# fasciaMainBoard_V0.net
KiCad netlist of a schematic drawn in EAGLE
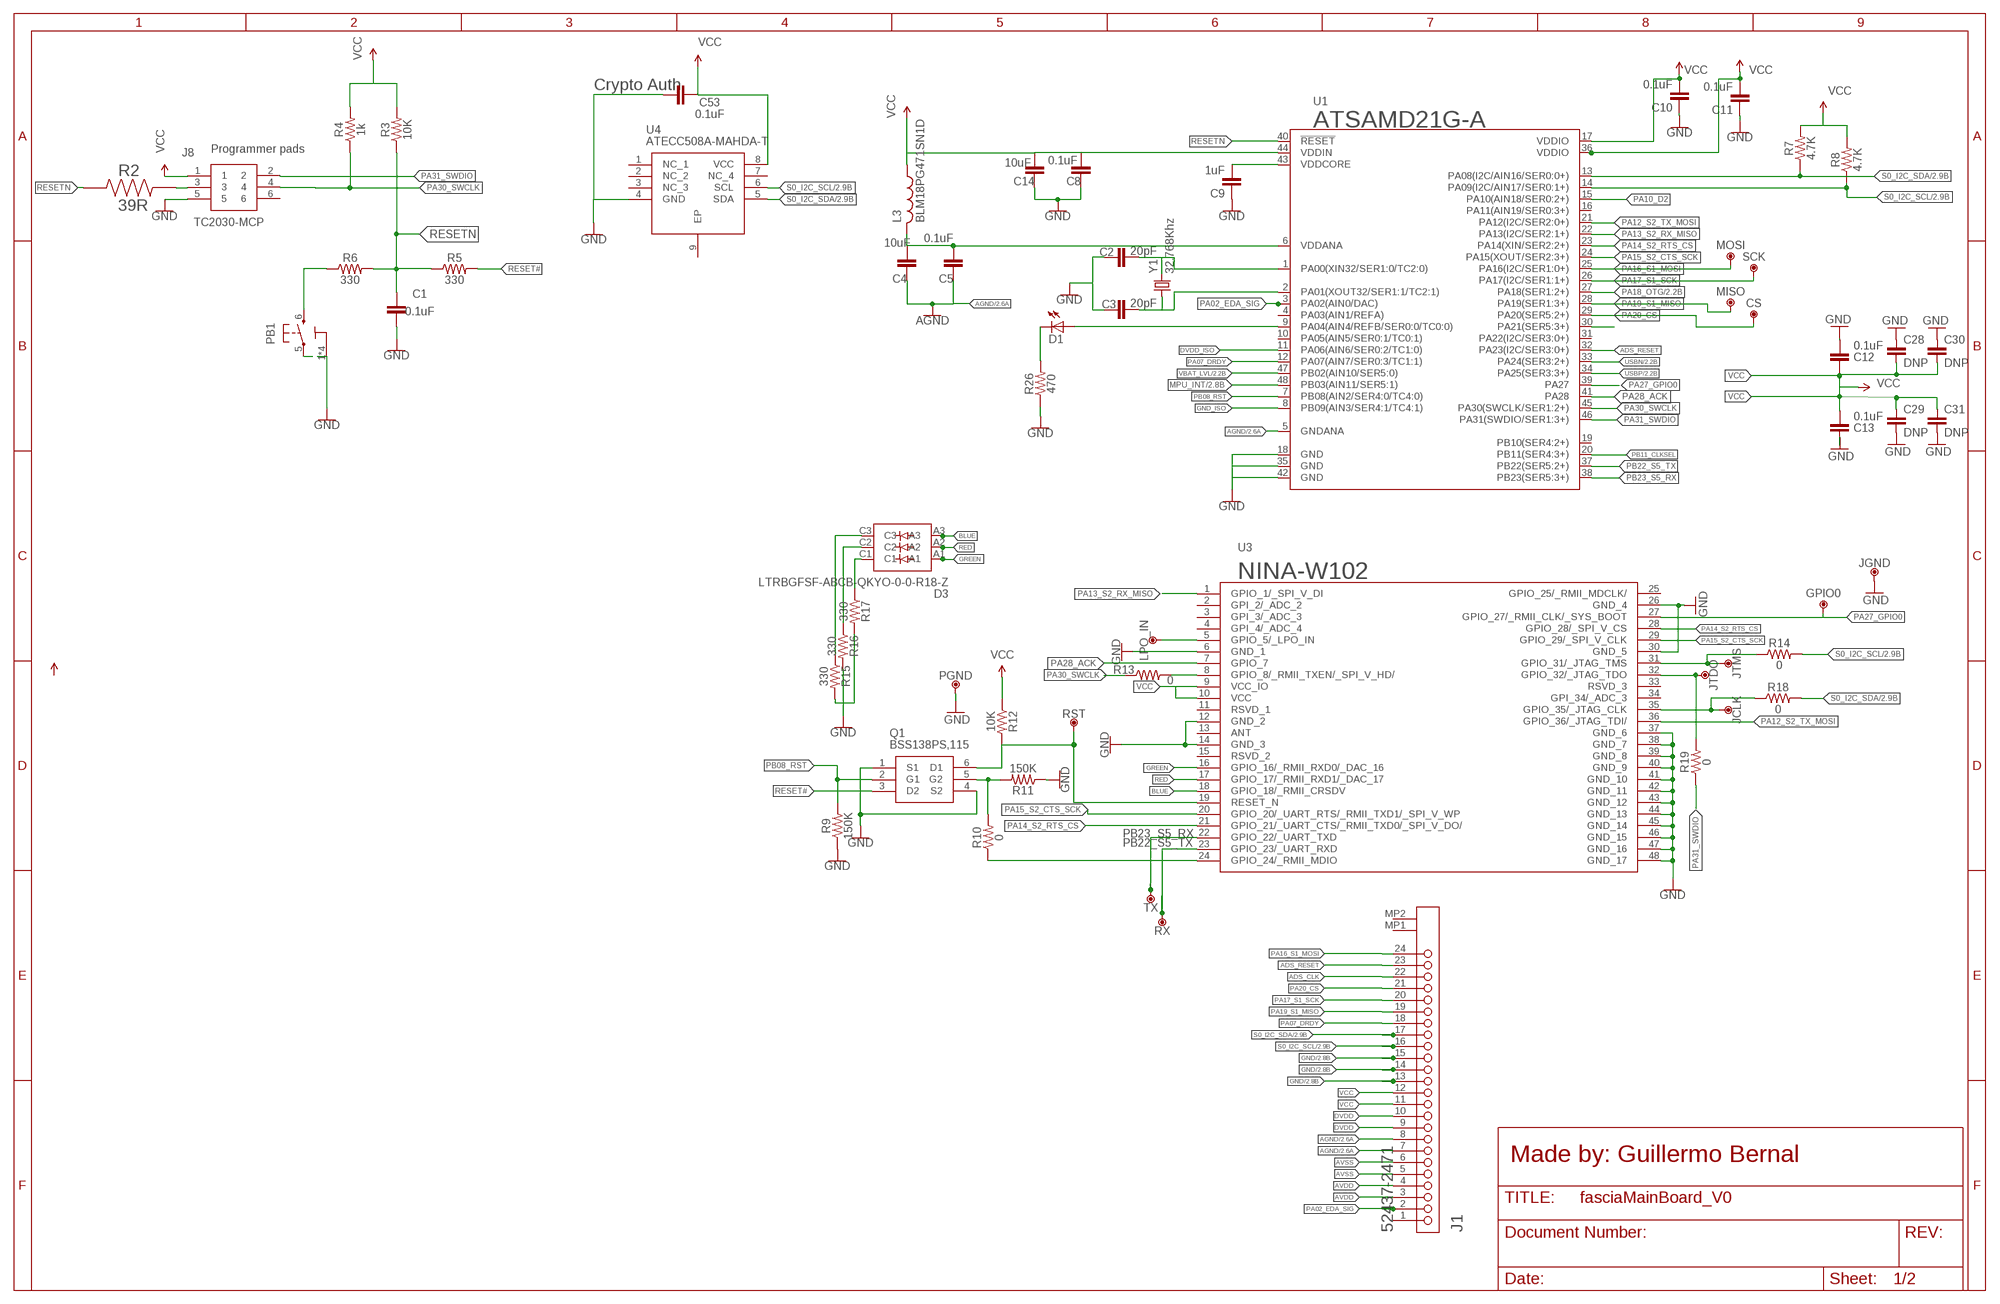
[diagram p0: schematic, sheet 1]
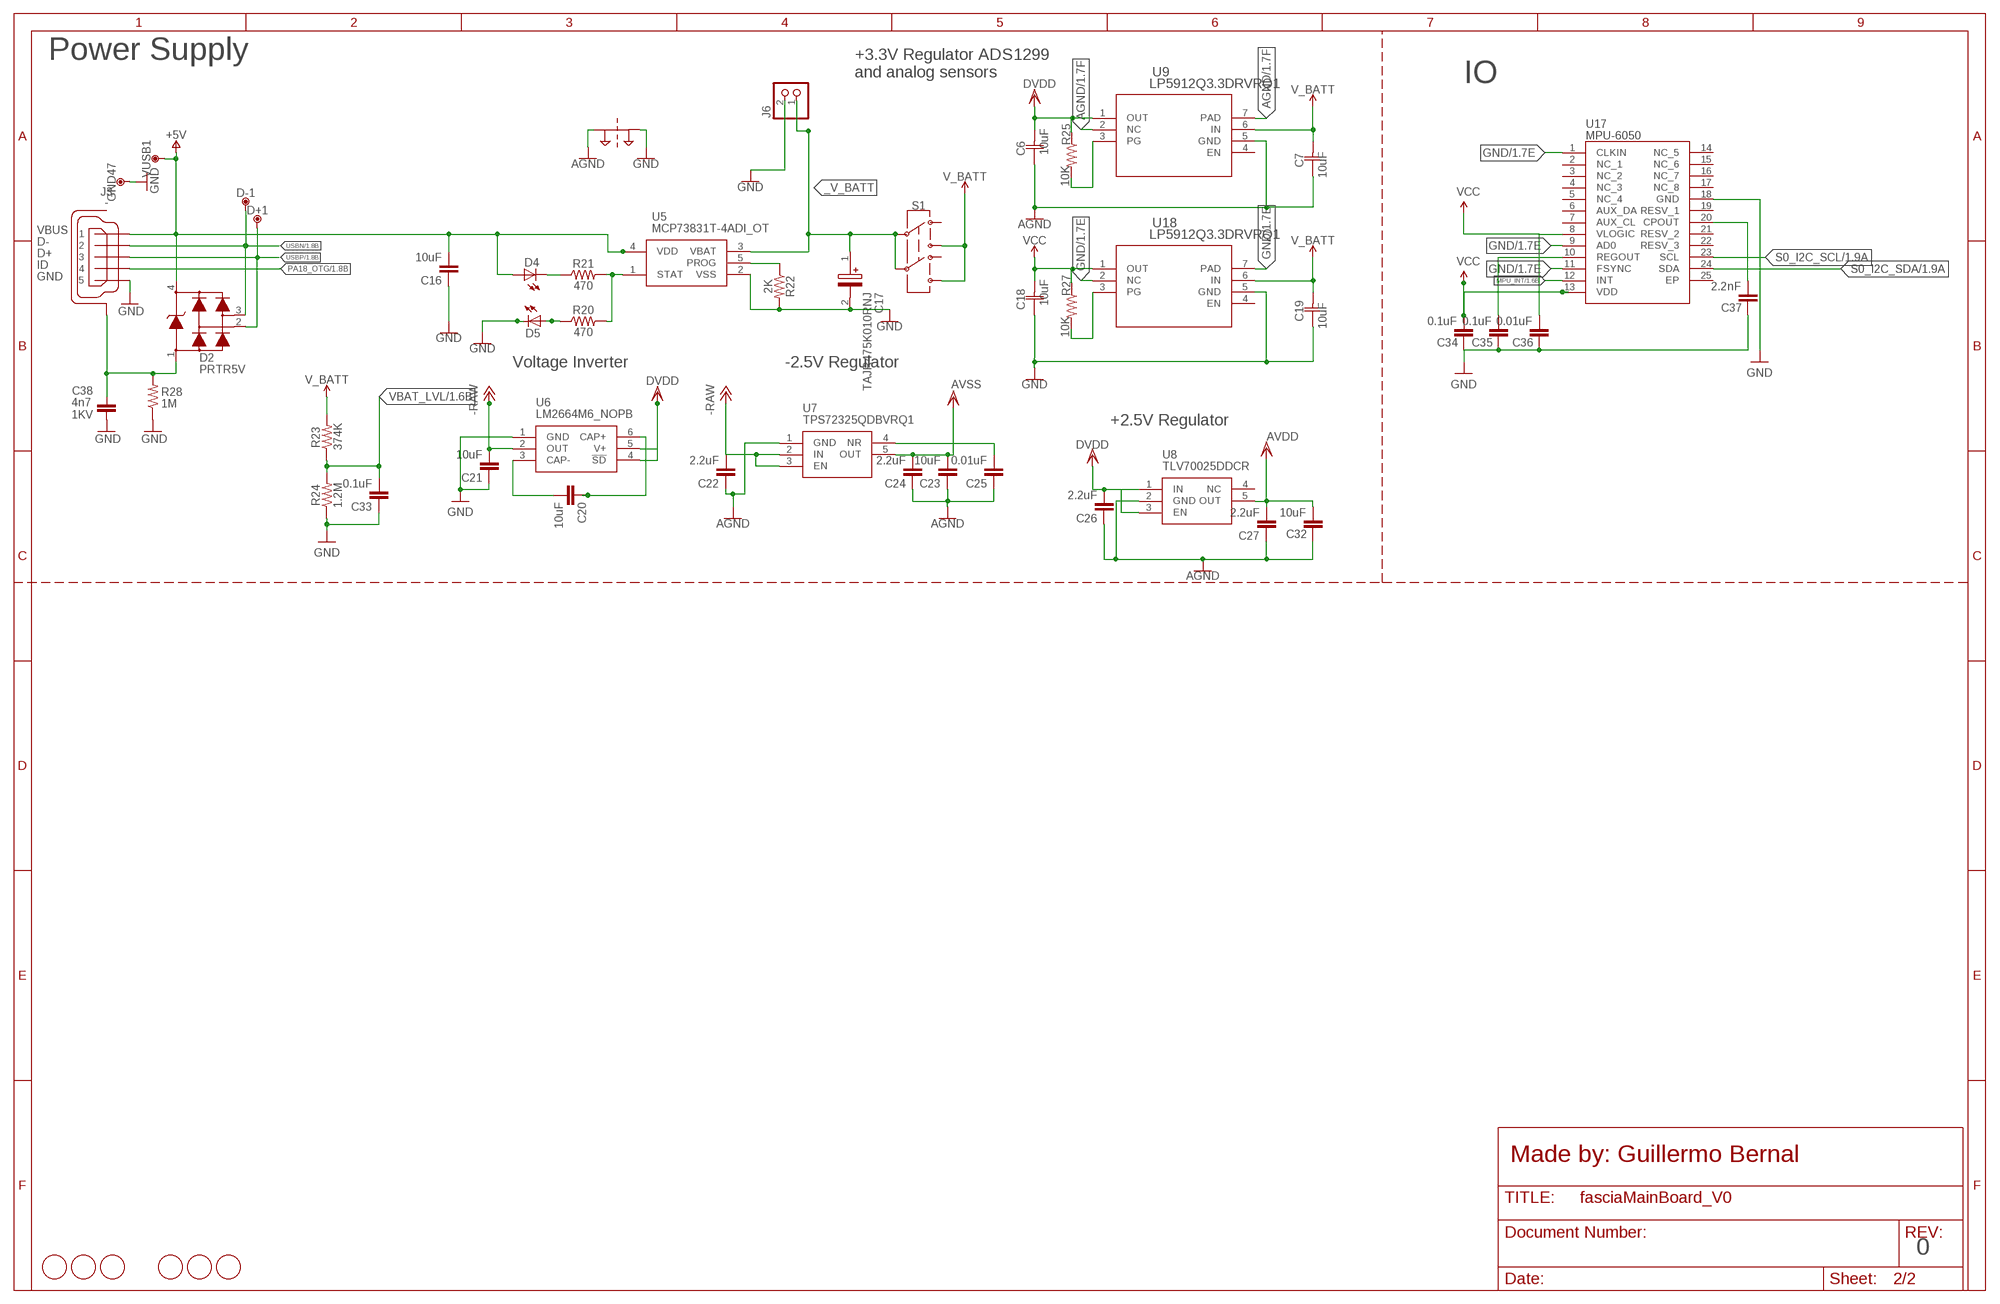
[diagram p1: schematic, sheet 2]

(export (version "E")
  (design (tool "Eeschema 10.0.6"))
  (components
    (comp (ref "C6")
      (value "10uF")
      (footprint "eagle-import:CAP_CL10-L")
      (fields (field (name "MANUFACTURER_PART_NUMBER") "CL10B106MQ8NRNC"))
      (libsource (lib "eagle-import") (part "CL10B106MQ8NRNCCAP_CL10-L"))
    )
    (comp (ref "C7")
      (value "10uF")
      (footprint "eagle-import:CAP_CL10-L")
      (fields (field (name "MANUFACTURER_PART_NUMBER") "CL10B106MQ8NRNC"))
      (libsource (lib "eagle-import") (part "CL10B106MQ8NRNCCAP_CL10-L"))
    )
    (comp (ref "C16")
      (value "10uF")
      (footprint "eagle-import:0603")
      (libsource (lib "eagle-import") (part "10UF-0603-6.3V-20%"))
    )
    (comp (ref "C17")
      (value "TAJR475K010RNJ")
      (footprint "eagle-import:CAPPM2014X120N")
      (fields
        (field (name "MOUSER_PART_NUMBER") "581-TAJR475K010R")
        (field (name "RS_PART_NUMBER") "1355409P")
      )
      (libsource (lib "eagle-import") (part "TAJR475K010RNJ"))
    )
    (comp (ref "C18")
      (value "10uF")
      (footprint "eagle-import:CAP_CL10-L")
      (fields (field (name "MANUFACTURER_PART_NUMBER") "CL10B106MQ8NRNC"))
      (libsource (lib "eagle-import") (part "CL10B106MQ8NRNCCAP_CL10-L"))
    )
    (comp (ref "C19")
      (value "10uF")
      (footprint "eagle-import:CAP_CL10-L")
      (fields (field (name "MANUFACTURER_PART_NUMBER") "CL10B106MQ8NRNC"))
      (libsource (lib "eagle-import") (part "CL10B106MQ8NRNCCAP_CL10-L"))
    )
    (comp (ref "C20")
      (value "10uF")
      (footprint "eagle-import:0603")
      (libsource (lib "eagle-import") (part "10UF-0603-6.3V-20%"))
    )
    (comp (ref "C21")
      (value "10uF")
      (footprint "eagle-import:0603")
      (libsource (lib "eagle-import") (part "10UF-0603-6.3V-20%"))
    )
    (comp (ref "C22")
      (value "2.2uF")
      (footprint "eagle-import:0402-TIGHT")
      (libsource (lib "eagle-import") (part "2.2UF-0402T-16V-10%"))
    )
    (comp (ref "C23")
      (value "10uF")
      (footprint "eagle-import:0603")
      (libsource (lib "eagle-import") (part "10UF-0603-6.3V-20%"))
    )
    (comp (ref "C24")
      (value "2.2uF")
      (footprint "eagle-import:0402-TIGHT")
      (libsource (lib "eagle-import") (part "2.2UF-0402T-16V-10%"))
    )
    (comp (ref "C25")
      (value "0.01uF")
      (footprint "eagle-import:0402-TIGHT")
      (libsource (lib "eagle-import") (part "0.01UF-0402T-16V-10%"))
    )
    (comp (ref "C26")
      (value "2.2uF")
      (footprint "eagle-import:0402-TIGHT")
      (libsource (lib "eagle-import") (part "2.2UF-0402T-16V-10%"))
    )
    (comp (ref "C27")
      (value "2.2uF")
      (footprint "eagle-import:0402-TIGHT")
      (libsource (lib "eagle-import") (part "2.2UF-0402T-16V-10%"))
    )
    (comp (ref "C32")
      (value "10uF")
      (footprint "eagle-import:0603")
      (libsource (lib "eagle-import") (part "10UF-0603-6.3V-20%"))
    )
    (comp (ref "C33")
      (value "0.1uF")
      (footprint "eagle-import:0402-TIGHT")
      (libsource (lib "eagle-import") (part "0.1UF-0402T-16V-10%"))
    )
    (comp (ref "C34")
      (value "0.1uF")
      (footprint "eagle-import:0402-TIGHT")
      (libsource (lib "eagle-import") (part "0.1UF-0402T-16V-10%"))
    )
    (comp (ref "C35")
      (value "0.1uF")
      (footprint "eagle-import:0402-TIGHT")
      (libsource (lib "eagle-import") (part "0.1UF-0402T-16V-10%"))
    )
    (comp (ref "C36")
      (value "0.01uF")
      (footprint "eagle-import:0402-TIGHT")
      (libsource (lib "eagle-import") (part "0.01UF-0402T-16V-10%"))
    )
    (comp (ref "C37")
      (value "2.2nF")
      (footprint "eagle-import:0402-TIGHT")
      (libsource (lib "eagle-import") (part "2.2NF-0402T-16V-10%"))
    )
    (comp (ref "C38")
      (value "4n7")
      (footprint "eagle-import:0805-R2013X50N")
      (fields (field (name "MANUFACTURER") "Kemet") (field (name "VOLTAGE") "1KV"))
      (libsource (lib "eagle-import") (part "C-08054.7NF"))
    )
    (comp (ref "D+1")
      (value "DNP")
      (footprint "eagle-import:TP-1.00MM")
      (libsource (lib "eagle-import") (part "TPTP-1.00MM"))
    )
    (comp (ref "D-1")
      (value "DNP")
      (footprint "eagle-import:TP-1.00MM")
      (libsource (lib "eagle-import") (part "TPTP-1.00MM"))
    )
    (comp (ref "D2")
      (value "PRTR5V")
      (footprint "eagle-import:SOT190P230X110-4N")
      (fields (field (name "MANUFACTURER") "NXP"))
      (libsource (lib "eagle-import") (part "PRTR5V0U2X,215"))
    )
    (comp (ref "D4")
      (value "LEDCHIPLED_0603")
      (footprint "eagle-import:CHIPLED_0603")
      (libsource (lib "eagle-import") (part "LEDCHIPLED_0603"))
    )
    (comp (ref "D5")
      (value "LEDCHIPLED_0603")
      (footprint "eagle-import:CHIPLED_0603")
      (libsource (lib "eagle-import") (part "LEDCHIPLED_0603"))
    )
    (comp (ref "FD1")
      (value "DNP")
      (footprint "eagle-import:FD-1-1.5")
      (libsource (lib "eagle-import") (part "FIDUCIAL-1.5MM"))
    )
    (comp (ref "FD2")
      (value "DNP")
      (footprint "eagle-import:FD-1-1.5")
      (libsource (lib "eagle-import") (part "FIDUCIAL-1.5MM"))
    )
    (comp (ref "FD3")
      (value "DNP")
      (footprint "eagle-import:FD-1-1.5")
      (libsource (lib "eagle-import") (part "FIDUCIAL-1.5MM"))
    )
    (comp (ref "FD4")
      (value "DNP")
      (footprint "eagle-import:FD-1-1.5")
      (libsource (lib "eagle-import") (part "FIDUCIAL-1.5MM"))
    )
    (comp (ref "FD5")
      (value "DNP")
      (footprint "eagle-import:FD-1-1.5")
      (libsource (lib "eagle-import") (part "FIDUCIAL-1.5MM"))
    )
    (comp (ref "FD6")
      (value "DNP")
      (footprint "eagle-import:FD-1-1.5")
      (libsource (lib "eagle-import") (part "FIDUCIAL-1.5MM"))
    )
    (comp (ref "GND47")
      (value "DNP")
      (footprint "eagle-import:TP-1.00MM")
      (libsource (lib "eagle-import") (part "TPTP-1.00MM"))
    )
    (comp (ref "J3")
      (value "-")
      (footprint "eagle-import:ZX62-AB-5PA")
      (fields (field (name "MANUFACTURER") "Hirose"))
      (libsource (lib "eagle-import") (part "USB-MICRO"))
    )
    (comp (ref "J6")
      (value "JST_2PIN-SMT-RA")
      (footprint "eagle-import:JST-PH-2-SMT-RA")
      (libsource (lib "eagle-import") (part "JST_2PIN-SMT-RA"))
    )
    (comp (ref "R20")
      (value "470")
      (footprint "eagle-import:0402-TIGHT")
      (libsource (lib "eagle-import") (part "470"))
    )
    (comp (ref "R21")
      (value "470")
      (footprint "eagle-import:0402-TIGHT")
      (libsource (lib "eagle-import") (part "470"))
    )
    (comp (ref "R22")
      (value "2K")
      (footprint "eagle-import:0402-TIGHT")
      (libsource (lib "eagle-import") (part "2K"))
    )
    (comp (ref "R23")
      (value "374K")
      (footprint "eagle-import:0402-TIGHT")
      (libsource (lib "eagle-import") (part "374K"))
    )
    (comp (ref "R24")
      (value "1.2M")
      (footprint "eagle-import:0402")
      (libsource (lib "eagle-import") (part "1.2M-0402-1/10W-1%"))
    )
    (comp (ref "R25")
      (value "10K")
      (footprint "eagle-import:0402-TIGHT")
      (libsource (lib "eagle-import") (part "10K"))
    )
    (comp (ref "R27")
      (value "10K")
      (footprint "eagle-import:0402-TIGHT")
      (libsource (lib "eagle-import") (part "10K"))
    )
    (comp (ref "R28")
      (value "1M")
      (footprint "eagle-import:0402-TIGHT")
      (libsource (lib "eagle-import") (part "1M"))
    )
    (comp (ref "S1")
      (value "SWITCH-DPDT-SMD-AYZ0202")
      (footprint "eagle-import:SWITCH_DPDT_SMD_AYZ0202")
      (libsource (lib "eagle-import") (part "SWITCH-DPDT-SMD-AYZ0202"))
    )
    (comp (ref "SUPPLY1")
      (value "2PT_GND_TIE")
      (footprint "eagle-import:2PT_GND_TIE")
      (libsource (lib "eagle-import") (part "2PT_GND_TIE"))
    )
    (comp (ref "U5")
      (value "MCP73831T-4ADI_OT")
      (footprint "eagle-import:SOT95P270X145-5N")
      (fields
        (field (name "MANUFACTURER_PART_NUMBER") "MCP73831T-4ADI/OT")
        (field (name "MOUSER_PART_NUMBER") "579-MCP73831T4ADIOT")
      )
      (libsource (lib "eagle-import") (part "MCP73831T-4ADI_OT"))
    )
    (comp (ref "U6")
      (value "LM2664M6_NOPB")
      (footprint "eagle-import:SOT95P280X145-6N")
      (fields
        (field (name "MANUFACTURER_PART_NUMBER") "LM2664M6/NOPB")
        (field (name "MOUSER_PART_NUMBER") "926-LM2664M6/NOPB")
        (field (name "RS_PART_NUMBER") "5358792P")
      )
      (libsource (lib "eagle-import") (part "LM2664M6_NOPB"))
    )
    (comp (ref "U7")
      (value "TPS72325QDBVRQ1")
      (footprint "eagle-import:SOT96P230X110-5N")
      (libsource (lib "eagle-import") (part "TPS72325QDBVRQ1"))
    )
    (comp (ref "U8")
      (value "TLV70025DDCR")
      (footprint "eagle-import:SOT95P280X110-5N")
      (fields (field (name "MOUSER_PART_NUMBER") "595-TLV70025DDCR"))
      (libsource (lib "eagle-import") (part "TLV70025DDCR"))
    )
    (comp (ref "U9")
      (value "LP5912Q3.3DRVRQ1")
      (footprint "eagle-import:DRV0006A")
      (libsource (lib "eagle-import") (part "LP5912Q3.3DRVRQ1"))
    )
    (comp (ref "U17")
      (value "MPU-6050")
      (footprint "eagle-import:MPU6050")
      (fields (field (name "MOUSER_PART_NUMBER") "410-MPU-6050"))
      (libsource (lib "eagle-import") (part "MPU-6050"))
    )
    (comp (ref "U18")
      (value "LP5912Q3.3DRVRQ1")
      (footprint "eagle-import:DRV0006A")
      (libsource (lib "eagle-import") (part "LP5912Q3.3DRVRQ1"))
    )
    (comp (ref "VUSB1")
      (value "DNP")
      (footprint "eagle-import:TP-1.00MM")
      (libsource (lib "eagle-import") (part "TPTP-1.00MM"))
    )
    (comp (ref "C1")
      (value "0.1uF")
      (footprint "eagle-import:0402-TIGHT")
      (libsource (lib "eagle-import") (part "0.1UF-0402T-16V-10%"))
    )
    (comp (ref "C2")
      (value "20pF")
      (footprint "eagle-import:0402-TIGHT")
      (libsource (lib "eagle-import") (part "20PF-0402T-16V-10%"))
    )
    (comp (ref "C3")
      (value "20pF")
      (footprint "eagle-import:0402-TIGHT")
      (libsource (lib "eagle-import") (part "20PF-0402T-16V-10%"))
    )
    (comp (ref "C4")
      (value "10uF")
      (footprint "eagle-import:0603")
      (libsource (lib "eagle-import") (part "SparkFun-Capacitors_510_10UF-0603-6.3V-20%"))
    )
    (comp (ref "C5")
      (value "0.1uF")
      (footprint "eagle-import:0402-TIGHT")
      (libsource (lib "eagle-import") (part "0.1UF-0402T-16V-10%"))
    )
    (comp (ref "C8")
      (value "0.1uF")
      (footprint "eagle-import:0402-TIGHT")
      (libsource (lib "eagle-import") (part "0.1UF-0402T-16V-10%"))
    )
    (comp (ref "C9")
      (value "1uF")
      (footprint "eagle-import:0402-TIGHT")
      (libsource (lib "eagle-import") (part "1UF-0402T-16V-10%"))
    )
    (comp (ref "C10")
      (value "0.1uF")
      (footprint "eagle-import:0402-TIGHT")
      (libsource (lib "eagle-import") (part "0.1UF-0402T-16V-10%"))
    )
    (comp (ref "C11")
      (value "0.1uF")
      (footprint "eagle-import:0402-TIGHT")
      (libsource (lib "eagle-import") (part "0.1UF-0402T-16V-10%"))
    )
    (comp (ref "C12")
      (value "0.1uF")
      (footprint "eagle-import:0402-TIGHT")
      (libsource (lib "eagle-import") (part "0.1UF-0402T-16V-10%"))
    )
    (comp (ref "C13")
      (value "0.1uF")
      (footprint "eagle-import:0402-TIGHT")
      (libsource (lib "eagle-import") (part "0.1UF-0402T-16V-10%"))
    )
    (comp (ref "C14")
      (value "10uF")
      (footprint "eagle-import:0603")
      (libsource (lib "eagle-import") (part "SparkFun-Capacitors_510_10UF-0603-6.3V-20%"))
    )
    (comp (ref "C28")
      (value "DNP")
      (footprint "eagle-import:0402-1005X55N")
      (libsource (lib "eagle-import") (part "C-0402DNP"))
    )
    (comp (ref "C29")
      (value "DNP")
      (footprint "eagle-import:0402-1005X55N")
      (libsource (lib "eagle-import") (part "C-0402DNP"))
    )
    (comp (ref "C30")
      (value "DNP")
      (footprint "eagle-import:0603-1608X90N")
      (libsource (lib "eagle-import") (part "C-0603-DNP"))
    )
    (comp (ref "C31")
      (value "DNP")
      (footprint "eagle-import:0603-1608X90N")
      (libsource (lib "eagle-import") (part "C-0603-DNP"))
    )
    (comp (ref "C53")
      (value "0.1uF")
      (footprint "eagle-import:0402-TIGHT")
      (libsource (lib "eagle-import") (part "0.1UF-0402T-16V-10%"))
    )
    (comp (ref "CS")
      (value "DNP")
      (footprint "eagle-import:TP-0.8MM")
      (libsource (lib "eagle-import") (part "TPTP-0.8MM"))
    )
    (comp (ref "D1")
      (value "LEDCHIPLED_0603")
      (footprint "eagle-import:CHIPLED_0603")
      (libsource (lib "eagle-import") (part "LEDCHIPLED_0603"))
    )
    (comp (ref "D3")
      (value "LTRBGFSF-ABCB-QKYO-0-0-R18-Z")
      (footprint "eagle-import:PLCC-6")
      (libsource (lib "eagle-import") (part "LTRBGFSF-ABCB-QKYO-0-0-R18-Z"))
    )
    (comp (ref "GPIO0")
      (value "DNP")
      (footprint "eagle-import:TP-0.8MM")
      (libsource (lib "eagle-import") (part "TPTP-0.8MM"))
    )
    (comp (ref "J1")
      (value "MOLEX_52437-2471MOLEX_52437-2471_0_0")
      (footprint "eagle-import:MOLEX_52437-2471_0")
      (fields (field (name "MF") "Molex") (field (name "MPN") "52437-2471"))
      (libsource (lib "eagle-import") (part "MOLEX_52437-2471MOLEX_52437-2471_0_0"))
    )
    (comp (ref "J8")
      (value "TC2030-MCP")
      (footprint "eagle-import:TC2030MCP")
      (fields (field (name "MOUSER_PART_NUMBER") "579-TC2030-MCP") (field (name "RS_PART_NUMBER") "8252568"))
      (libsource (lib "eagle-import") (part "TC2030-MCP"))
    )
    (comp (ref "JCLK")
      (value "DNP")
      (footprint "eagle-import:TP-0.8MM")
      (libsource (lib "eagle-import") (part "TPTP-0.8MM"))
    )
    (comp (ref "JGND")
      (value "DNP")
      (footprint "eagle-import:TP-0.8MM")
      (libsource (lib "eagle-import") (part "TPTP-0.8MM"))
    )
    (comp (ref "JTDO")
      (value "DNP")
      (footprint "eagle-import:TP-0.8MM")
      (libsource (lib "eagle-import") (part "TPTP-0.8MM"))
    )
    (comp (ref "JTMS")
      (value "DNP")
      (footprint "eagle-import:TP-0.8MM")
      (libsource (lib "eagle-import") (part "TPTP-0.8MM"))
    )
    (comp (ref "L3")
      (value "BLM18PG471SN1D")
      (footprint "eagle-import:BEADC1608X95N")
      (fields
        (field (name "MOUSER_PART_NUMBER") "81-BLM18PG471SN1D")
        (field (name "RS_PART_NUMBER") "7241425P")
      )
      (libsource (lib "eagle-import") (part "BLM18PG471SN1D"))
    )
    (comp (ref "LPO_IN")
      (value "DNP")
      (footprint "eagle-import:TP-0.8MM")
      (libsource (lib "eagle-import") (part "TPTP-0.8MM"))
    )
    (comp (ref "MISO")
      (value "DNP")
      (footprint "eagle-import:TP-0.8MM")
      (libsource (lib "eagle-import") (part "TPTP-0.8MM"))
    )
    (comp (ref "MOSI")
      (value "DNP")
      (footprint "eagle-import:TP-0.8MM")
      (libsource (lib "eagle-import") (part "TPTP-0.8MM"))
    )
    (comp (ref "PB1")
      (value "PTS820")
      (footprint "eagle-import:C&K_PTS820_NO_HOLES")
      (fields (field (name "MANUFACTURER") "C&K"))
      (libsource (lib "eagle-import") (part "TACTILE1PTS820-NH"))
    )
    (comp (ref "PGND")
      (value "DNP")
      (footprint "eagle-import:TP-0.8MM")
      (libsource (lib "eagle-import") (part "TPTP-0.8MM"))
    )
    (comp (ref "Q1")
      (value "BSS138PS,115")
      (footprint "eagle-import:SOT65P210X110-6N")
      (fields
        (field (name "MOUSER_PART_NUMBER") "771-BSS138PS115")
        (field (name "RS_PART_NUMBER") "7920901P")
      )
      (libsource (lib "eagle-import") (part "BSS138PS,115"))
    )
    (comp (ref "R2")
      (value "39R")
      (footprint "eagle-import:RESC1005X40N")
      (fields (field (name "MF") "Yageo") (field (name "MP") "RC0402FR-0739RL"))
      (libsource (lib "eagle-import") (part "RC0402FR-0739RL"))
    )
    (comp (ref "R3")
      (value "10K")
      (footprint "eagle-import:0402-TIGHT")
      (libsource (lib "eagle-import") (part "10K"))
    )
    (comp (ref "R4")
      (value "1k")
      (footprint "eagle-import:0402-TIGHT")
      (libsource (lib "eagle-import") (part "1K"))
    )
    (comp (ref "R5")
      (value "330")
      (footprint "eagle-import:0402-TIGHT")
      (libsource (lib "eagle-import") (part "330"))
    )
    (comp (ref "R6")
      (value "330")
      (footprint "eagle-import:0402-TIGHT")
      (libsource (lib "eagle-import") (part "330"))
    )
    (comp (ref "R7")
      (value "4.7K")
      (footprint "eagle-import:0402-TIGHT")
      (libsource (lib "eagle-import") (part "4.7K"))
    )
    (comp (ref "R8")
      (value "4.7K")
      (footprint "eagle-import:0402-TIGHT")
      (libsource (lib "eagle-import") (part "4.7K"))
    )
    (comp (ref "R9")
      (value "150K")
      (footprint "eagle-import:0402-TIGHT")
      (libsource (lib "eagle-import") (part "100K"))
    )
    (comp (ref "R10")
      (value "0")
      (footprint "eagle-import:0402-TIGHT")
      (libsource (lib "eagle-import") (part "0"))
    )
    (comp (ref "R11")
      (value "150K")
      (footprint "eagle-import:0402-TIGHT")
      (libsource (lib "eagle-import") (part "100K"))
    )
    (comp (ref "R12")
      (value "10K")
      (footprint "eagle-import:0402-TIGHT")
      (libsource (lib "eagle-import") (part "10K"))
    )
    (comp (ref "R13")
      (value "0")
      (footprint "eagle-import:0402-TIGHT")
      (libsource (lib "eagle-import") (part "0"))
    )
    (comp (ref "R14")
      (value "0")
      (footprint "eagle-import:0402-TIGHT")
      (libsource (lib "eagle-import") (part "0"))
    )
    (comp (ref "R15")
      (value "330")
      (footprint "eagle-import:0402-TIGHT")
      (libsource (lib "eagle-import") (part "330"))
    )
    (comp (ref "R16")
      (value "330")
      (footprint "eagle-import:0402-TIGHT")
      (libsource (lib "eagle-import") (part "330"))
    )
    (comp (ref "R17")
      (value "330")
      (footprint "eagle-import:0402-TIGHT")
      (libsource (lib "eagle-import") (part "330"))
    )
    (comp (ref "R18")
      (value "0")
      (footprint "eagle-import:0402-TIGHT")
      (libsource (lib "eagle-import") (part "0"))
    )
    (comp (ref "R19")
      (value "0")
      (footprint "eagle-import:0402-TIGHT")
      (libsource (lib "eagle-import") (part "0"))
    )
    (comp (ref "R26")
      (value "470")
      (footprint "eagle-import:0402-TIGHT")
      (libsource (lib "eagle-import") (part "470"))
    )
    (comp (ref "RST")
      (value "DNP")
      (footprint "eagle-import:TP-0.8MM")
      (libsource (lib "eagle-import") (part "TPTP-0.8MM"))
    )
    (comp (ref "RX")
      (value "DNP")
      (footprint "eagle-import:TP-0.8MM")
      (libsource (lib "eagle-import") (part "TPTP-0.8MM"))
    )
    (comp (ref "SCK")
      (value "DNP")
      (footprint "eagle-import:TP-0.8MM")
      (libsource (lib "eagle-import") (part "TPTP-0.8MM"))
    )
    (comp (ref "TX")
      (value "DNP")
      (footprint "eagle-import:TP-0.8MM")
      (libsource (lib "eagle-import") (part "TPTP-0.8MM"))
    )
    (comp (ref "U1")
      (value "ATSAMD21G-A")
      (footprint "eagle-import:TQFP-48")
      (libsource (lib "eagle-import") (part "ATSAMD21G-A"))
    )
    (comp (ref "U3")
      (value "NINA-W102")
      (footprint "eagle-import:NINAW102")
      (libsource (lib "eagle-import") (part "NINA-W102"))
    )
    (comp (ref "U4")
      (value "ATECC508A-MAHDA-T")
      (footprint "eagle-import:SON50P300X200X60-9N")
      (fields
        (field (name "MOUSER_PART_NUMBER") "556-ATECC508A-MAHDAT")
        (field (name "RS_PART_NUMBER") "1773144P")
      )
      (libsource (lib "eagle-import") (part "ATECC508A-MAHDA-T"))
    )
    (comp (ref "Y1")
      (value "32.768Khz")
      (footprint "eagle-import:ECX-31B")
      (fields
        (field (name "MANUFACTURER_PART_NUMBER") "ECS-.327-12.5-34B-TR")
        (field (name "MOUSER_PART_NUMBER") "520-327-12.5-34B")
      )
      (libsource (lib "eagle-import") (part "ECS-.327-12.5-34B-TR"))
    )
  )
  (nets
    (net (code "1") (name "+5V") (class "Default")
      (node (ref "C16") (pin "2") (pinfunction "2_2") (pintype "passive"))
      (node (ref "D2") (pin "4") (pinfunction "4_4") (pintype "passive"))
      (node (ref "D4") (pin "A") (pinfunction "A_A") (pintype "passive"))
      (node (ref "J3") (pin "1") (pinfunction "1_1") (pintype "passive"))
      (node (ref "U5") (pin "4") (pinfunction "VDD_4") (pintype "bidirectional"))
      (node (ref "VUSB1") (pin "X") (pinfunction "P$1_X") (pintype "passive"))
    )
    (net (code "2") (name "-RAW") (class "Default")
      (node (ref "C21") (pin "2") (pinfunction "2_2") (pintype "passive"))
      (node (ref "C22") (pin "2") (pinfunction "2_2") (pintype "passive"))
      (node (ref "U6") (pin "2") (pinfunction "OUT_2") (pintype "output"))
      (node (ref "U7") (pin "2") (pinfunction "IN_2") (pintype "power_in"))
      (node (ref "U7") (pin "3") (pinfunction "EN_3") (pintype "bidirectional"))
    )
    (net (code "3") (name "ADS_CLK") (class "Default")
      (node (ref "J1") (pin "22") (pinfunction "22_22") (pintype "passive"))
    )
    (net (code "4") (name "ADS_RESET") (class "Default")
      (node (ref "J1") (pin "23") (pinfunction "23_23") (pintype "passive"))
      (node (ref "U1") (pin "32") (pinfunction "PA23(I2C/SER3:0+)_32") (pintype "bidirectional"))
    )
    (net (code "5") (name "AGND") (class "Default")
      (node (ref "C22") (pin "1") (pinfunction "1_1") (pintype "passive"))
      (node (ref "C23") (pin "1") (pinfunction "1_1") (pintype "passive"))
      (node (ref "C24") (pin "1") (pinfunction "1_1") (pintype "passive"))
      (node (ref "C25") (pin "1") (pinfunction "1_1") (pintype "passive"))
      (node (ref "C26") (pin "1") (pinfunction "1_1") (pintype "passive"))
      (node (ref "C27") (pin "1") (pinfunction "1_1") (pintype "passive"))
      (node (ref "C32") (pin "1") (pinfunction "1_1") (pintype "passive"))
      (node (ref "C4") (pin "1") (pinfunction "1_1") (pintype "passive"))
      (node (ref "C5") (pin "1") (pinfunction "1_1") (pintype "passive"))
      (node (ref "C6") (pin "1") (pinfunction "1_1") (pintype "passive"))
      (node (ref "C7") (pin "1") (pinfunction "1_1") (pintype "passive"))
      (node (ref "J1") (pin "7") (pinfunction "7_7") (pintype "passive"))
      (node (ref "J1") (pin "8") (pinfunction "8_8") (pintype "passive"))
      (node (ref "SUPPLY1") (pin "P$1") (pinfunction "P$1_P$1") (pintype "bidirectional"))
      (node (ref "U1") (pin "5") (pinfunction "GNDANA_5") (pintype "bidirectional"))
      (node (ref "U7") (pin "1") (pinfunction "GND_1") (pintype "power_in"))
      (node (ref "U8") (pin "2") (pinfunction "GND_2") (pintype "bidirectional"))
      (node (ref "U9") (pin "2") (pinfunction "NC_2") (pintype "passive"))
      (node (ref "U9") (pin "5") (pinfunction "GND_5") (pintype "power_in"))
      (node (ref "U9") (pin "7") (pinfunction "PAD_7") (pintype "power_in"))
    )
    (net (code "6") (name "AVDD") (class "Default")
      (node (ref "C27") (pin "2") (pinfunction "2_2") (pintype "passive"))
      (node (ref "C32") (pin "2") (pinfunction "2_2") (pintype "passive"))
      (node (ref "J1") (pin "3") (pinfunction "3_3") (pintype "passive"))
      (node (ref "J1") (pin "4") (pinfunction "4_4") (pintype "passive"))
      (node (ref "U8") (pin "5") (pinfunction "OUT_5") (pintype "bidirectional"))
    )
    (net (code "7") (name "AVSS") (class "Default")
      (node (ref "C23") (pin "2") (pinfunction "2_2") (pintype "passive"))
      (node (ref "C24") (pin "2") (pinfunction "2_2") (pintype "passive"))
      (node (ref "J1") (pin "5") (pinfunction "5_5") (pintype "passive"))
      (node (ref "J1") (pin "6") (pinfunction "6_6") (pintype "passive"))
      (node (ref "U7") (pin "5") (pinfunction "OUT_5") (pintype "power_in"))
    )
    (net (code "8") (name "BLUE") (class "Default")
      (node (ref "D3") (pin "A3") (pinfunction "A3_A3") (pintype "bidirectional"))
      (node (ref "U3") (pin "18") (pinfunction "GPIO_18/_RMII_CRSDV_18") (pintype "bidirectional"))
    )
    (net (code "9") (name "DVDD") (class "Default")
      (node (ref "C26") (pin "2") (pinfunction "2_2") (pintype "passive"))
      (node (ref "C6") (pin "2") (pinfunction "2_2") (pintype "passive"))
      (node (ref "J1") (pin "10") (pinfunction "10_10") (pintype "passive"))
      (node (ref "J1") (pin "9") (pinfunction "9_9") (pintype "passive"))
      (node (ref "R25") (pin "1") (pinfunction "1_1") (pintype "passive"))
      (node (ref "U6") (pin "4") (pinfunction "~{SD}_4") (pintype "input"))
      (node (ref "U6") (pin "5") (pinfunction "V+_5") (pintype "power_in"))
      (node (ref "U8") (pin "1") (pinfunction "IN_1") (pintype "bidirectional"))
      (node (ref "U8") (pin "3") (pinfunction "EN_3") (pintype "bidirectional"))
      (node (ref "U9") (pin "1") (pinfunction "OUT_1") (pintype "power_in"))
    )
    (net (code "10") (name "DVDD_ISO") (class "Default")
      (node (ref "U1") (pin "11") (pinfunction "PA06(AIN6/SER0:2/TC1:0)_11") (pintype "bidirectional"))
    )
    (net (code "11") (name "GND") (class "Default")
      (node (ref "C1") (pin "2") (pinfunction "2_2") (pintype "passive"))
      (node (ref "C10") (pin "1") (pinfunction "1_1") (pintype "passive"))
      (node (ref "C11") (pin "1") (pinfunction "1_1") (pintype "passive"))
      (node (ref "C12") (pin "2") (pinfunction "2_2") (pintype "passive"))
      (node (ref "C13") (pin "1") (pinfunction "1_1") (pintype "passive"))
      (node (ref "C14") (pin "1") (pinfunction "1_1") (pintype "passive"))
      (node (ref "C16") (pin "1") (pinfunction "1_1") (pintype "passive"))
      (node (ref "C17") (pin "2") (pinfunction "-_2") (pintype "bidirectional"))
      (node (ref "C18") (pin "1") (pinfunction "1_1") (pintype "passive"))
      (node (ref "C19") (pin "1") (pinfunction "1_1") (pintype "passive"))
      (node (ref "C2") (pin "1") (pinfunction "1_1") (pintype "passive"))
      (node (ref "C21") (pin "1") (pinfunction "1_1") (pintype "passive"))
      (node (ref "C28") (pin "1") (pinfunction "1_1") (pintype "passive"))
      (node (ref "C29") (pin "2") (pinfunction "2_2") (pintype "passive"))
      (node (ref "C3") (pin "1") (pinfunction "1_1") (pintype "passive"))
      (node (ref "C30") (pin "1") (pinfunction "1_1") (pintype "passive"))
      (node (ref "C31") (pin "2") (pinfunction "2_2") (pintype "passive"))
      (node (ref "C33") (pin "1") (pinfunction "1_1") (pintype "passive"))
      (node (ref "C34") (pin "1") (pinfunction "1_1") (pintype "passive"))
      (node (ref "C35") (pin "1") (pinfunction "1_1") (pintype "passive"))
      (node (ref "C36") (pin "1") (pinfunction "1_1") (pintype "passive"))
      (node (ref "C37") (pin "1") (pinfunction "1_1") (pintype "passive"))
      (node (ref "C38") (pin "2") (pinfunction "2_2") (pintype "passive"))
      (node (ref "C53") (pin "2") (pinfunction "2_2") (pintype "passive"))
      (node (ref "C8") (pin "1") (pinfunction "1_1") (pintype "passive"))
      (node (ref "C9") (pin "1") (pinfunction "1_1") (pintype "passive"))
      (node (ref "D5") (pin "C") (pinfunction "C_C") (pintype "passive"))
      (node (ref "GND47") (pin "X") (pinfunction "P$1_X") (pintype "passive"))
      (node (ref "J1") (pin "13") (pinfunction "13_13") (pintype "passive"))
      (node (ref "J1") (pin "14") (pinfunction "14_14") (pintype "passive"))
      (node (ref "J1") (pin "15") (pinfunction "15_15") (pintype "passive"))
      (node (ref "J3") (pin "5") (pinfunction "5_5") (pintype "passive"))
      (node (ref "J6") (pin "2") (pinfunction "1_2") (pintype "passive"))
      (node (ref "J8") (pin "5") (pinfunction "5_5") (pintype "bidirectional"))
      (node (ref "JGND") (pin "X") (pinfunction "P$1_X") (pintype "passive"))
      (node (ref "PB1") (pin "1") (pinfunction "3_1") (pintype "power_in"))
      (node (ref "PB1") (pin "2") (pinfunction "3_2") (pintype "power_in"))
      (node (ref "PB1") (pin "3") (pinfunction "3_3") (pintype "power_in"))
      (node (ref "PB1") (pin "4") (pinfunction "3_4") (pintype "power_in"))
      (node (ref "PB1") (pin "5") (pinfunction "1_5") (pintype "passive"))
      (node (ref "PGND") (pin "X") (pinfunction "P$1_X") (pintype "passive"))
      (node (ref "Q1") (pin "1") (pinfunction "S1_1") (pintype "bidirectional"))
      (node (ref "Q1") (pin "4") (pinfunction "S2_4") (pintype "bidirectional"))
      (node (ref "R11") (pin "1") (pinfunction "1_1") (pintype "passive"))
      (node (ref "R15") (pin "2") (pinfunction "2_2") (pintype "passive"))
      (node (ref "R16") (pin "2") (pinfunction "2_2") (pintype "passive"))
      (node (ref "R17") (pin "2") (pinfunction "2_2") (pintype "passive"))
      (node (ref "R22") (pin "2") (pinfunction "2_2") (pintype "passive"))
      (node (ref "R24") (pin "1") (pinfunction "1_1") (pintype "passive"))
      (node (ref "R26") (pin "1") (pinfunction "1_1") (pintype "passive"))
      (node (ref "R28") (pin "1") (pinfunction "1_1") (pintype "passive"))
      (node (ref "R9") (pin "1") (pinfunction "1_1") (pintype "passive"))
      (node (ref "SUPPLY1") (pin "P$2") (pinfunction "P$2_P$2") (pintype "bidirectional"))
      (node (ref "U1") (pin "18") (pinfunction "GND_18") (pintype "bidirectional"))
      (node (ref "U1") (pin "35") (pinfunction "GND_35") (pintype "bidirectional"))
      (node (ref "U1") (pin "42") (pinfunction "GND_42") (pintype "bidirectional"))
      (node (ref "U17") (pin "1") (pinfunction "CLKIN_1") (pintype "bidirectional"))
      (node (ref "U17") (pin "11") (pinfunction "FSYNC_11") (pintype "bidirectional"))
      (node (ref "U17") (pin "18") (pinfunction "GND_18") (pintype "bidirectional"))
      (node (ref "U17") (pin "9") (pinfunction "AD0_9") (pintype "bidirectional"))
      (node (ref "U18") (pin "2") (pinfunction "NC_2") (pintype "passive"))
      (node (ref "U18") (pin "5") (pinfunction "GND_5") (pintype "power_in"))
      (node (ref "U18") (pin "7") (pinfunction "PAD_7") (pintype "power_in"))
      (node (ref "U3") (pin "12") (pinfunction "GND_2_12") (pintype "bidirectional"))
      (node (ref "U3") (pin "14") (pinfunction "GND_3_14") (pintype "bidirectional"))
      (node (ref "U3") (pin "26") (pinfunction "GND_4_26") (pintype "bidirectional"))
      (node (ref "U3") (pin "30") (pinfunction "GND_5_30") (pintype "bidirectional"))
      (node (ref "U3") (pin "37") (pinfunction "GND_6_37") (pintype "bidirectional"))
      (node (ref "U3") (pin "38") (pinfunction "GND_7_38") (pintype "bidirectional"))
      (node (ref "U3") (pin "39") (pinfunction "GND_8_39") (pintype "bidirectional"))
      (node (ref "U3") (pin "40") (pinfunction "GND_9_40") (pintype "bidirectional"))
      (node (ref "U3") (pin "41") (pinfunction "GND_10_41") (pintype "bidirectional"))
      (node (ref "U3") (pin "42") (pinfunction "GND_11_42") (pintype "bidirectional"))
      (node (ref "U3") (pin "43") (pinfunction "GND_12_43") (pintype "bidirectional"))
      (node (ref "U3") (pin "44") (pinfunction "GND_13_44") (pintype "bidirectional"))
      (node (ref "U3") (pin "45") (pinfunction "GND_14_45") (pintype "bidirectional"))
      (node (ref "U3") (pin "46") (pinfunction "GND_15_46") (pintype "bidirectional"))
      (node (ref "U3") (pin "47") (pinfunction "GND_16_47") (pintype "bidirectional"))
      (node (ref "U3") (pin "48") (pinfunction "GND_17_48") (pintype "bidirectional"))
      (node (ref "U3") (pin "6") (pinfunction "GND_1_6") (pintype "bidirectional"))
      (node (ref "U4") (pin "4") (pinfunction "GND_4") (pintype "bidirectional"))
      (node (ref "U5") (pin "2") (pinfunction "VSS_2") (pintype "bidirectional"))
      (node (ref "U6") (pin "1") (pinfunction "GND_1") (pintype "power_in"))
    )
    (net (code "12") (name "GND_ISO") (class "Default")
      (node (ref "U1") (pin "8") (pinfunction "PB09(AIN3/SER4:1/TC4:1)_8") (pintype "bidirectional"))
    )
    (net (code "13") (name "GREEN") (class "Default")
      (node (ref "D3") (pin "A1") (pinfunction "A1_A1") (pintype "bidirectional"))
      (node (ref "U3") (pin "16") (pinfunction "GPIO_16/_RMII_RXD0/_DAC_16_16") (pintype "bidirectional"))
    )
    (net (code "14") (name "MPU_INT") (class "Default")
      (node (ref "U1") (pin "48") (pinfunction "PB03(AIN11/SER5:1)_48") (pintype "bidirectional"))
      (node (ref "U17") (pin "12") (pinfunction "INT_12") (pintype "bidirectional"))
    )
    (net (code "15") (name "Net-(C38-Pad1)") (class "Default")
      (node (ref "C38") (pin "1") (pinfunction "1_1") (pintype "passive"))
      (node (ref "D2") (pin "1") (pinfunction "1_1") (pintype "passive"))
      (node (ref "J3") (pin "10") (pinfunction "SH_10") (pintype "passive"))
      (node (ref "J3") (pin "11") (pinfunction "SH_11") (pintype "passive"))
      (node (ref "J3") (pin "6") (pinfunction "SH_6") (pintype "passive"))
      (node (ref "J3") (pin "7") (pinfunction "SH_7") (pintype "passive"))
      (node (ref "J3") (pin "8") (pinfunction "SH_8") (pintype "passive"))
      (node (ref "J3") (pin "9") (pinfunction "SH_9") (pintype "passive"))
      (node (ref "R28") (pin "2") (pinfunction "2_2") (pintype "passive"))
    )
    (net (code "16") (name "Net-(D1-PadC)") (class "Default")
      (node (ref "D1") (pin "C") (pinfunction "C_C") (pintype "passive"))
      (node (ref "R26") (pin "2") (pinfunction "2_2") (pintype "passive"))
    )
    (net (code "17") (name "Net-(D3-PadC1)") (class "Default")
      (node (ref "D3") (pin "C1") (pinfunction "C1_C1") (pintype "bidirectional"))
      (node (ref "R17") (pin "1") (pinfunction "1_1") (pintype "passive"))
    )
    (net (code "18") (name "Net-(D3-PadC2)") (class "Default")
      (node (ref "D3") (pin "C2") (pinfunction "C2_C2") (pintype "bidirectional"))
      (node (ref "R16") (pin "1") (pinfunction "1_1") (pintype "passive"))
    )
    (net (code "19") (name "Net-(D3-PadC3)") (class "Default")
      (node (ref "D3") (pin "C3") (pinfunction "C3_C3") (pintype "bidirectional"))
      (node (ref "R15") (pin "1") (pinfunction "1_1") (pintype "passive"))
    )
    (net (code "20") (name "Net-(D4-PadC)") (class "Default")
      (node (ref "D4") (pin "C") (pinfunction "C_C") (pintype "passive"))
      (node (ref "R21") (pin "1") (pinfunction "1_1") (pintype "passive"))
    )
    (net (code "21") (name "Net-(D5-PadA)") (class "Default")
      (node (ref "D5") (pin "A") (pinfunction "A_A") (pintype "passive"))
      (node (ref "R20") (pin "1") (pinfunction "1_1") (pintype "passive"))
    )
    (net (code "22") (name "Net-(J8-Pad3)") (class "Default")
      (node (ref "J8") (pin "3") (pinfunction "3_3") (pintype "bidirectional"))
      (node (ref "R2") (pin "2") (pinfunction "2_2") (pintype "passive"))
    )
    (net (code "23") (name "Net-(JCLK-P$1)") (class "Default")
      (node (ref "JCLK") (pin "X") (pinfunction "P$1_X") (pintype "passive"))
      (node (ref "R18") (pin "1") (pinfunction "1_1") (pintype "passive"))
      (node (ref "U3") (pin "35") (pinfunction "GPIO_35/_JTAG_CLK_35") (pintype "bidirectional"))
    )
    (net (code "24") (name "Net-(JTDO-P$1)") (class "Default")
      (node (ref "JTDO") (pin "X") (pinfunction "P$1_X") (pintype "passive"))
      (node (ref "R19") (pin "2") (pinfunction "2_2") (pintype "passive"))
      (node (ref "U3") (pin "32") (pinfunction "GPIO_32/_JTAG_TDO_32") (pintype "bidirectional"))
    )
    (net (code "25") (name "Net-(JTMS-P$1)") (class "Default")
      (node (ref "JTMS") (pin "X") (pinfunction "P$1_X") (pintype "passive"))
      (node (ref "R14") (pin "1") (pinfunction "1_1") (pintype "passive"))
      (node (ref "U3") (pin "31") (pinfunction "GPIO_31/_JTAG_TMS_31") (pintype "bidirectional"))
    )
    (net (code "26") (name "Net-(LPO_IN-P$1)") (class "Default")
      (node (ref "LPO_IN") (pin "X") (pinfunction "P$1_X") (pintype "passive"))
      (node (ref "U3") (pin "5") (pinfunction "GPIO_5/_LPO_IN_5") (pintype "bidirectional"))
    )
    (net (code "27") (name "Net-(PB1-2)") (class "Default")
      (node (ref "PB1") (pin "6") (pinfunction "2_6") (pintype "passive"))
      (node (ref "R6") (pin "1") (pinfunction "1_1") (pintype "passive"))
    )
    (net (code "28") (name "Net-(Q1-D1)") (class "Default")
      (node (ref "Q1") (pin "6") (pinfunction "D1_6") (pintype "bidirectional"))
      (node (ref "R12") (pin "2") (pinfunction "2_2") (pintype "passive"))
      (node (ref "RST") (pin "X") (pinfunction "P$1_X") (pintype "passive"))
      (node (ref "U3") (pin "19") (pinfunction "RESET_N_19") (pintype "bidirectional"))
    )
    (net (code "29") (name "Net-(Q1-G2)") (class "Default")
      (node (ref "Q1") (pin "5") (pinfunction "G2_5") (pintype "bidirectional"))
      (node (ref "R10") (pin "2") (pinfunction "2_2") (pintype "passive"))
      (node (ref "R11") (pin "2") (pinfunction "2_2") (pintype "passive"))
    )
    (net (code "30") (name "Net-(U1-PA00(XIN32{slash}SER1:0{slash}TC2:0))") (class "Default")
      (node (ref "C2") (pin "2") (pinfunction "2_2") (pintype "passive"))
      (node (ref "U1") (pin "1") (pinfunction "PA00(XIN32/SER1:0/TC2:0)_1") (pintype "bidirectional"))
      (node (ref "Y1") (pin "2") (pinfunction "2_2") (pintype "passive"))
    )
    (net (code "31") (name "Net-(U1-PA01(XOUT32{slash}SER1:1{slash}TC2:1))") (class "Default")
      (node (ref "C3") (pin "2") (pinfunction "2_2") (pintype "passive"))
      (node (ref "U1") (pin "2") (pinfunction "PA01(XOUT32/SER1:1/TC2:1)_2") (pintype "bidirectional"))
      (node (ref "Y1") (pin "1") (pinfunction "1_1") (pintype "passive"))
    )
    (net (code "32") (name "Net-(U1-PA04(AIN4{slash}REFB{slash}SER0:0{slash}TC0:0))") (class "Default")
      (node (ref "D1") (pin "A") (pinfunction "A_A") (pintype "passive"))
      (node (ref "U1") (pin "9") (pinfunction "PA04(AIN4/REFB/SER0:0/TC0:0)_9") (pintype "bidirectional"))
    )
    (net (code "33") (name "Net-(U1-VDDANA)") (class "Default")
      (node (ref "C4") (pin "2") (pinfunction "2_2") (pintype "passive"))
      (node (ref "C5") (pin "2") (pinfunction "2_2") (pintype "passive"))
      (node (ref "L3") (pin "2") (pinfunction "2_2") (pintype "passive"))
      (node (ref "U1") (pin "6") (pinfunction "VDDANA_6") (pintype "bidirectional"))
    )
    (net (code "34") (name "Net-(U1-VDDCORE)") (class "Default")
      (node (ref "C9") (pin "2") (pinfunction "2_2") (pintype "passive"))
      (node (ref "U1") (pin "43") (pinfunction "VDDCORE_43") (pintype "bidirectional"))
    )
    (net (code "35") (name "Net-(U3-GPIO_8{slash}_RMII_TXEN{slash}_SPI_V_HD{slash})") (class "Default")
      (node (ref "R13") (pin "2") (pinfunction "2_2") (pintype "passive"))
      (node (ref "U3") (pin "8") (pinfunction "GPIO_8/_RMII_TXEN/_SPI_V_HD/_8") (pintype "bidirectional"))
    )
    (net (code "36") (name "Net-(U3-GPIO_24{slash}_RMII_MDIO)") (class "Default")
      (node (ref "R10") (pin "1") (pinfunction "1_1") (pintype "passive"))
      (node (ref "U3") (pin "24") (pinfunction "GPIO_24/_RMII_MDIO_24") (pintype "bidirectional"))
    )
    (net (code "37") (name "Net-(U5-PROG)") (class "Default")
      (node (ref "R22") (pin "1") (pinfunction "1_1") (pintype "passive"))
      (node (ref "U5") (pin "5") (pinfunction "PROG_5") (pintype "bidirectional"))
    )
    (net (code "38") (name "Net-(U5-STAT)") (class "Default")
      (node (ref "R20") (pin "2") (pinfunction "2_2") (pintype "passive"))
      (node (ref "R21") (pin "2") (pinfunction "2_2") (pintype "passive"))
      (node (ref "U5") (pin "1") (pinfunction "STAT_1") (pintype "bidirectional"))
    )
    (net (code "39") (name "Net-(U6-CAP+)") (class "Default")
      (node (ref "C20") (pin "1") (pinfunction "1_1") (pintype "passive"))
      (node (ref "U6") (pin "6") (pinfunction "CAP+_6") (pintype "power_in"))
    )
    (net (code "40") (name "Net-(U6-CAP-)") (class "Default")
      (node (ref "C20") (pin "2") (pinfunction "2_2") (pintype "passive"))
      (node (ref "U6") (pin "3") (pinfunction "CAP-_3") (pintype "power_in"))
    )
    (net (code "41") (name "Net-(U7-NR)") (class "Default")
      (node (ref "C25") (pin "2") (pinfunction "2_2") (pintype "passive"))
      (node (ref "U7") (pin "4") (pinfunction "NR_4") (pintype "bidirectional"))
    )
    (net (code "42") (name "Net-(U9-PG)") (class "Default")
      (node (ref "R25") (pin "2") (pinfunction "2_2") (pintype "passive"))
      (node (ref "U9") (pin "3") (pinfunction "PG_3") (pintype "output"))
    )
    (net (code "43") (name "Net-(U17-CPOUT)") (class "Default")
      (node (ref "C37") (pin "2") (pinfunction "2_2") (pintype "passive"))
      (node (ref "U17") (pin "20") (pinfunction "CPOUT_20") (pintype "bidirectional"))
    )
    (net (code "44") (name "Net-(U17-REGOUT)") (class "Default")
      (node (ref "C35") (pin "2") (pinfunction "2_2") (pintype "passive"))
      (node (ref "U17") (pin "10") (pinfunction "REGOUT_10") (pintype "bidirectional"))
    )
    (net (code "45") (name "Net-(U18-PG)") (class "Default")
      (node (ref "R27") (pin "2") (pinfunction "2_2") (pintype "passive"))
      (node (ref "U18") (pin "3") (pinfunction "PG_3") (pintype "output"))
    )
    (net (code "46") (name "PA02_EDA_SIG") (class "Default")
      (node (ref "J1") (pin "2") (pinfunction "2_2") (pintype "passive"))
      (node (ref "U1") (pin "3") (pinfunction "PA02(AIN0/DAC)_3") (pintype "bidirectional"))
    )
    (net (code "47") (name "PA07_DRDY") (class "Default")
      (node (ref "J1") (pin "18") (pinfunction "18_18") (pintype "passive"))
      (node (ref "U1") (pin "12") (pinfunction "PA07(AIN7/SER0:3/TC1:1)_12") (pintype "bidirectional"))
    )
    (net (code "48") (name "PA10_D2") (class "Default")
      (node (ref "U1") (pin "15") (pinfunction "PA10(AIN18/SER0:2+)_15") (pintype "bidirectional"))
    )
    (net (code "49") (name "PA12_S2_TX_MOSI") (class "Default")
      (node (ref "U1") (pin "21") (pinfunction "PA12(I2C/SER2:0+)_21") (pintype "bidirectional"))
      (node (ref "U3") (pin "36") (pinfunction "GPIO_36/_JTAG_TDI/_36") (pintype "bidirectional"))
    )
    (net (code "50") (name "PA13_S2_RX_MISO") (class "Default")
      (node (ref "U1") (pin "22") (pinfunction "PA13(I2C/SER2:1+)_22") (pintype "bidirectional"))
      (node (ref "U3") (pin "1") (pinfunction "GPIO_1/_SPI_V_DI_1") (pintype "bidirectional"))
    )
    (net (code "51") (name "PA14_S2_RTS_CS") (class "Default")
      (node (ref "U1") (pin "23") (pinfunction "PA14(XIN/SER2:2+)_23") (pintype "bidirectional"))
      (node (ref "U3") (pin "21") (pinfunction "GPIO_21/_UART_CTS/_RMII_TXD0/_SPI_V_DO/_21") (pintype "bidirectional"))
      (node (ref "U3") (pin "28") (pinfunction "GPIO_28/_SPI_V_CS_28") (pintype "bidirectional"))
    )
    (net (code "52") (name "PA15_S2_CTS_SCK") (class "Default")
      (node (ref "U1") (pin "24") (pinfunction "PA15(XOUT/SER2:3+)_24") (pintype "bidirectional"))
      (node (ref "U3") (pin "20") (pinfunction "GPIO_20/_UART_RTS/_RMII_TXD1/_SPI_V_WP_20") (pintype "bidirectional"))
      (node (ref "U3") (pin "29") (pinfunction "GPIO_29/_SPI_V_CLK_29") (pintype "bidirectional"))
    )
    (net (code "53") (name "PA16_S1_MOSI") (class "Default")
      (node (ref "J1") (pin "24") (pinfunction "24_24") (pintype "passive"))
      (node (ref "MOSI") (pin "X") (pinfunction "P$1_X") (pintype "passive"))
      (node (ref "U1") (pin "25") (pinfunction "PA16(I2C/SER1:0+)_25") (pintype "bidirectional"))
    )
    (net (code "54") (name "PA17_S1_SCK") (class "Default")
      (node (ref "J1") (pin "20") (pinfunction "20_20") (pintype "passive"))
      (node (ref "SCK") (pin "X") (pinfunction "P$1_X") (pintype "passive"))
      (node (ref "U1") (pin "26") (pinfunction "PA17(I2C/SER1:1+)_26") (pintype "bidirectional"))
    )
    (net (code "55") (name "PA18_OTG") (class "Default")
      (node (ref "J3") (pin "4") (pinfunction "4_4") (pintype "passive"))
      (node (ref "U1") (pin "27") (pinfunction "PA18(SER1:2+)_27") (pintype "bidirectional"))
    )
    (net (code "56") (name "PA19_S1_MISO") (class "Default")
      (node (ref "J1") (pin "19") (pinfunction "19_19") (pintype "passive"))
      (node (ref "MISO") (pin "X") (pinfunction "P$1_X") (pintype "passive"))
      (node (ref "U1") (pin "28") (pinfunction "PA19(SER1:3+)_28") (pintype "bidirectional"))
    )
    (net (code "57") (name "PA20_CS") (class "Default")
      (node (ref "CS") (pin "X") (pinfunction "P$1_X") (pintype "passive"))
      (node (ref "J1") (pin "21") (pinfunction "21_21") (pintype "passive"))
      (node (ref "U1") (pin "29") (pinfunction "PA20(SER5:2+)_29") (pintype "bidirectional"))
    )
    (net (code "58") (name "PA27_GPIO0") (class "Default")
      (node (ref "GPIO0") (pin "X") (pinfunction "P$1_X") (pintype "passive"))
      (node (ref "U1") (pin "39") (pinfunction "PA27_39") (pintype "bidirectional"))
      (node (ref "U3") (pin "27") (pinfunction "GPIO_27/_RMII_CLK/_SYS_BOOT_27") (pintype "bidirectional"))
    )
    (net (code "59") (name "PA28_ACK") (class "Default")
      (node (ref "U1") (pin "41") (pinfunction "PA28_41") (pintype "bidirectional"))
      (node (ref "U3") (pin "7") (pinfunction "GPIO_7_7") (pintype "bidirectional"))
    )
    (net (code "60") (name "PA30_SWCLK") (class "Default")
      (node (ref "J8") (pin "4") (pinfunction "4_4") (pintype "bidirectional"))
      (node (ref "R13") (pin "1") (pinfunction "1_1") (pintype "passive"))
      (node (ref "R4") (pin "1") (pinfunction "1_1") (pintype "passive"))
      (node (ref "U1") (pin "45") (pinfunction "PA30(SWCLK/SER1:2+)_45") (pintype "bidirectional"))
    )
    (net (code "61") (name "PA31_SWDIO") (class "Default")
      (node (ref "J8") (pin "2") (pinfunction "2_2") (pintype "bidirectional"))
      (node (ref "R19") (pin "1") (pinfunction "1_1") (pintype "passive"))
      (node (ref "U1") (pin "46") (pinfunction "PA31(SWDIO/SER1:3+)_46") (pintype "bidirectional"))
    )
    (net (code "62") (name "PB08_RST") (class "Default")
      (node (ref "Q1") (pin "2") (pinfunction "G1_2") (pintype "bidirectional"))
      (node (ref "R9") (pin "2") (pinfunction "2_2") (pintype "passive"))
      (node (ref "U1") (pin "7") (pinfunction "PB08(AIN2/SER4:0/TC4:0)_7") (pintype "bidirectional"))
    )
    (net (code "63") (name "PB11_CLKSEL") (class "Default")
      (node (ref "U1") (pin "20") (pinfunction "PB11(SER4:3+)_20") (pintype "bidirectional"))
    )
    (net (code "64") (name "PB22_S5_TX") (class "Default")
      (node (ref "RX") (pin "X") (pinfunction "P$1_X") (pintype "passive"))
      (node (ref "U1") (pin "37") (pinfunction "PB22(SER5:2+)_37") (pintype "bidirectional"))
      (node (ref "U3") (pin "23") (pinfunction "GPIO_23/_UART_RXD_23") (pintype "bidirectional"))
    )
    (net (code "65") (name "PB23_S5_RX") (class "Default")
      (node (ref "TX") (pin "X") (pinfunction "P$1_X") (pintype "passive"))
      (node (ref "U1") (pin "38") (pinfunction "PB23(SER5:3+)_38") (pintype "bidirectional"))
      (node (ref "U3") (pin "22") (pinfunction "GPIO_22/_UART_TXD_22") (pintype "bidirectional"))
    )
    (net (code "66") (name "RED") (class "Default")
      (node (ref "D3") (pin "A2") (pinfunction "A2_A2") (pintype "bidirectional"))
      (node (ref "U3") (pin "17") (pinfunction "GPIO_17/_RMII_RXD1/_DAC_17_17") (pintype "bidirectional"))
    )
    (net (code "67") (name "RESET#") (class "Default")
      (node (ref "Q1") (pin "3") (pinfunction "D2_3") (pintype "bidirectional"))
      (node (ref "R5") (pin "2") (pinfunction "2_2") (pintype "passive"))
    )
    (net (code "68") (name "RESETN") (class "Default")
      (node (ref "C1") (pin "1") (pinfunction "1_1") (pintype "passive"))
      (node (ref "R2") (pin "1") (pinfunction "1_1") (pintype "passive"))
      (node (ref "R3") (pin "1") (pinfunction "1_1") (pintype "passive"))
      (node (ref "R5") (pin "1") (pinfunction "1_1") (pintype "passive"))
      (node (ref "R6") (pin "2") (pinfunction "2_2") (pintype "passive"))
      (node (ref "U1") (pin "40") (pinfunction "~{RESET}_40") (pintype "bidirectional"))
    )
    (net (code "69") (name "S0_I2C_SCL") (class "Default")
      (node (ref "J1") (pin "16") (pinfunction "16_16") (pintype "passive"))
      (node (ref "R14") (pin "2") (pinfunction "2_2") (pintype "passive"))
      (node (ref "R8") (pin "1") (pinfunction "1_1") (pintype "passive"))
      (node (ref "U1") (pin "14") (pinfunction "PA09(I2C/AIN17/SER0:1+)_14") (pintype "bidirectional"))
      (node (ref "U17") (pin "23") (pinfunction "SCL_23") (pintype "bidirectional"))
      (node (ref "U4") (pin "6") (pinfunction "SCL_6") (pintype "bidirectional"))
    )
    (net (code "70") (name "S0_I2C_SDA") (class "Default")
      (node (ref "J1") (pin "17") (pinfunction "17_17") (pintype "passive"))
      (node (ref "R18") (pin "2") (pinfunction "2_2") (pintype "passive"))
      (node (ref "R7") (pin "1") (pinfunction "1_1") (pintype "passive"))
      (node (ref "U1") (pin "13") (pinfunction "PA08(I2C/AIN16/SER0:0+)_13") (pintype "bidirectional"))
      (node (ref "U17") (pin "24") (pinfunction "SDA_24") (pintype "bidirectional"))
      (node (ref "U4") (pin "5") (pinfunction "SDA_5") (pintype "bidirectional"))
    )
    (net (code "71") (name "USBN") (class "Default")
      (node (ref "D-1") (pin "X") (pinfunction "P$1_X") (pintype "passive"))
      (node (ref "D2") (pin "3") (pinfunction "3_3") (pintype "passive"))
      (node (ref "J3") (pin "2") (pinfunction "2_2") (pintype "passive"))
      (node (ref "U1") (pin "33") (pinfunction "PA24(SER3:2+)_33") (pintype "bidirectional"))
    )
    (net (code "72") (name "USBP") (class "Default")
      (node (ref "D+1") (pin "X") (pinfunction "P$1_X") (pintype "passive"))
      (node (ref "D2") (pin "2") (pinfunction "2_2") (pintype "passive"))
      (node (ref "J3") (pin "3") (pinfunction "3_3") (pintype "passive"))
      (node (ref "U1") (pin "34") (pinfunction "PA25(SER3:3+)_34") (pintype "bidirectional"))
    )
    (net (code "73") (name "VBAT_LVL") (class "Default")
      (node (ref "C33") (pin "2") (pinfunction "2_2") (pintype "passive"))
      (node (ref "R23") (pin "1") (pinfunction "1_1") (pintype "passive"))
      (node (ref "R24") (pin "2") (pinfunction "2_2") (pintype "passive"))
      (node (ref "U1") (pin "47") (pinfunction "PB02(AIN10/SER5:0)_47") (pintype "bidirectional"))
    )
    (net (code "74") (name "VCC") (class "Default")
      (node (ref "C10") (pin "2") (pinfunction "2_2") (pintype "passive"))
      (node (ref "C11") (pin "2") (pinfunction "2_2") (pintype "passive"))
      (node (ref "C12") (pin "1") (pinfunction "1_1") (pintype "passive"))
      (node (ref "C13") (pin "2") (pinfunction "2_2") (pintype "passive"))
      (node (ref "C14") (pin "2") (pinfunction "2_2") (pintype "passive"))
      (node (ref "C18") (pin "2") (pinfunction "2_2") (pintype "passive"))
      (node (ref "C28") (pin "2") (pinfunction "2_2") (pintype "passive"))
      (node (ref "C29") (pin "1") (pinfunction "1_1") (pintype "passive"))
      (node (ref "C30") (pin "2") (pinfunction "2_2") (pintype "passive"))
      (node (ref "C31") (pin "1") (pinfunction "1_1") (pintype "passive"))
      (node (ref "C34") (pin "2") (pinfunction "2_2") (pintype "passive"))
      (node (ref "C36") (pin "2") (pinfunction "2_2") (pintype "passive"))
      (node (ref "C53") (pin "1") (pinfunction "1_1") (pintype "passive"))
      (node (ref "C8") (pin "2") (pinfunction "2_2") (pintype "passive"))
      (node (ref "J1") (pin "11") (pinfunction "11_11") (pintype "passive"))
      (node (ref "J1") (pin "12") (pinfunction "12_12") (pintype "passive"))
      (node (ref "J8") (pin "1") (pinfunction "1_1") (pintype "bidirectional"))
      (node (ref "L3") (pin "1") (pinfunction "1_1") (pintype "passive"))
      (node (ref "R12") (pin "1") (pinfunction "1_1") (pintype "passive"))
      (node (ref "R27") (pin "1") (pinfunction "1_1") (pintype "passive"))
      (node (ref "R3") (pin "2") (pinfunction "2_2") (pintype "passive"))
      (node (ref "R4") (pin "2") (pinfunction "2_2") (pintype "passive"))
      (node (ref "R7") (pin "2") (pinfunction "2_2") (pintype "passive"))
      (node (ref "R8") (pin "2") (pinfunction "2_2") (pintype "passive"))
      (node (ref "U1") (pin "17") (pinfunction "VDDIO_17") (pintype "bidirectional"))
      (node (ref "U1") (pin "36") (pinfunction "VDDIO_36") (pintype "bidirectional"))
      (node (ref "U1") (pin "44") (pinfunction "VDDIN_44") (pintype "bidirectional"))
      (node (ref "U17") (pin "13") (pinfunction "VDD_13") (pintype "bidirectional"))
      (node (ref "U17") (pin "8") (pinfunction "VLOGIC_8") (pintype "bidirectional"))
      (node (ref "U18") (pin "1") (pinfunction "OUT_1") (pintype "power_in"))
      (node (ref "U3") (pin "10") (pinfunction "VCC_10") (pintype "bidirectional"))
      (node (ref "U3") (pin "9") (pinfunction "VCC_IO_9") (pintype "bidirectional"))
      (node (ref "U4") (pin "8") (pinfunction "VCC_8") (pintype "bidirectional"))
    )
    (net (code "75") (name "V_BATT") (class "Default")
      (node (ref "C19") (pin "2") (pinfunction "2_2") (pintype "passive"))
      (node (ref "C7") (pin "2") (pinfunction "2_2") (pintype "passive"))
      (node (ref "R23") (pin "2") (pinfunction "2_2") (pintype "passive"))
      (node (ref "S1") (pin "3") (pinfunction "3_3") (pintype "bidirectional"))
      (node (ref "S1") (pin "6") (pinfunction "6_6") (pintype "bidirectional"))
      (node (ref "U18") (pin "6") (pinfunction "IN_6") (pintype "power_in"))
      (node (ref "U9") (pin "6") (pinfunction "IN_6") (pintype "power_in"))
    )
    (net (code "76") (name "_V_BATT") (class "Default")
      (node (ref "C17") (pin "1") (pinfunction "+_1") (pintype "bidirectional"))
      (node (ref "J6") (pin "1") (pinfunction "2_1") (pintype "passive"))
      (node (ref "S1") (pin "2") (pinfunction "2_2") (pintype "bidirectional"))
      (node (ref "S1") (pin "5") (pinfunction "5_5") (pintype "bidirectional"))
      (node (ref "U5") (pin "3") (pinfunction "VBAT_3") (pintype "bidirectional"))
    )
    (net (code "77") (name "unconnected-(J1-Pad1)") (class "Default")
      (node (ref "J1") (pin "1") (pinfunction "1_1") (pintype "passive"))
    )
    (net (code "78") (name "unconnected-(J1-PadMP1)") (class "Default")
      (node (ref "J1") (pin "MP1") (pinfunction "MP1_MP1") (pintype "passive"))
    )
    (net (code "79") (name "unconnected-(J1-PadMP2)") (class "Default")
      (node (ref "J1") (pin "MP2") (pinfunction "MP2_MP2") (pintype "passive"))
    )
    (net (code "80") (name "unconnected-(J8-Pad6)") (class "Default")
      (node (ref "J8") (pin "6") (pinfunction "6_6") (pintype "bidirectional"))
    )
    (net (code "81") (name "unconnected-(S1-Pad1)") (class "Default")
      (node (ref "S1") (pin "1") (pinfunction "1_1") (pintype "bidirectional"))
    )
    (net (code "82") (name "unconnected-(S1-Pad4)") (class "Default")
      (node (ref "S1") (pin "4") (pinfunction "4_4") (pintype "bidirectional"))
    )
    (net (code "83") (name "unconnected-(U1-PA03(AIN1{slash}REFA)-Pad4)") (class "Default")
      (node (ref "U1") (pin "4") (pinfunction "PA03(AIN1/REFA)_4") (pintype "bidirectional"))
    )
    (net (code "84") (name "unconnected-(U1-PA05(AIN5{slash}SER0:1{slash}TC0:1)-Pad10)") (class "Default")
      (node (ref "U1") (pin "10") (pinfunction "PA05(AIN5/SER0:1/TC0:1)_10") (pintype "bidirectional"))
    )
    (net (code "85") (name "unconnected-(U1-PA11(AIN19{slash}SER0:3+)-Pad16)") (class "Default")
      (node (ref "U1") (pin "16") (pinfunction "PA11(AIN19/SER0:3+)_16") (pintype "bidirectional"))
    )
    (net (code "86") (name "unconnected-(U1-PA21(SER5:3+)-Pad30)") (class "Default")
      (node (ref "U1") (pin "30") (pinfunction "PA21(SER5:3+)_30") (pintype "bidirectional"))
    )
    (net (code "87") (name "unconnected-(U1-PA22(I2C{slash}SER3:0+)-Pad31)") (class "Default")
      (node (ref "U1") (pin "31") (pinfunction "PA22(I2C/SER3:0+)_31") (pintype "bidirectional"))
    )
    (net (code "88") (name "unconnected-(U1-PB10(SER4:2+)-Pad19)") (class "Default")
      (node (ref "U1") (pin "19") (pinfunction "PB10(SER4:2+)_19") (pintype "bidirectional"))
    )
    (net (code "89") (name "unconnected-(U3-ANT-Pad13)") (class "Default")
      (node (ref "U3") (pin "13") (pinfunction "ANT_13") (pintype "bidirectional"))
    )
    (net (code "90") (name "unconnected-(U3-GPIO_25{slash}_RMII_MDCLK{slash}-Pad25)") (class "Default")
      (node (ref "U3") (pin "25") (pinfunction "GPIO_25/_RMII_MDCLK/_25") (pintype "bidirectional"))
    )
    (net (code "91") (name "unconnected-(U3-GPI_2{slash}_ADC_2-Pad2)") (class "Default")
      (node (ref "U3") (pin "2") (pinfunction "GPI_2/_ADC_2_2") (pintype "bidirectional"))
    )
    (net (code "92") (name "unconnected-(U3-GPI_3{slash}_ADC_3-Pad3)") (class "Default")
      (node (ref "U3") (pin "3") (pinfunction "GPI_3/_ADC_3_3") (pintype "bidirectional"))
    )
    (net (code "93") (name "unconnected-(U3-GPI_4{slash}_ADC_4-Pad4)") (class "Default")
      (node (ref "U3") (pin "4") (pinfunction "GPI_4/_ADC_4_4") (pintype "bidirectional"))
    )
    (net (code "94") (name "unconnected-(U3-GPI_34{slash}_ADC_3-Pad34)") (class "Default")
      (node (ref "U3") (pin "34") (pinfunction "GPI_34/_ADC_3_34") (pintype "bidirectional"))
    )
    (net (code "95") (name "unconnected-(U3-RSVD_1-Pad11)") (class "Default")
      (node (ref "U3") (pin "11") (pinfunction "RSVD_1_11") (pintype "bidirectional"))
    )
    (net (code "96") (name "unconnected-(U3-RSVD_2-Pad15)") (class "Default")
      (node (ref "U3") (pin "15") (pinfunction "RSVD_2_15") (pintype "bidirectional"))
    )
    (net (code "97") (name "unconnected-(U3-RSVD_3-Pad33)") (class "Default")
      (node (ref "U3") (pin "33") (pinfunction "RSVD_3_33") (pintype "bidirectional"))
    )
    (net (code "98") (name "unconnected-(U4-EP-Pad9)") (class "Default")
      (node (ref "U4") (pin "9") (pinfunction "EP_9") (pintype "bidirectional"))
    )
    (net (code "99") (name "unconnected-(U4-NC_1-Pad1)") (class "Default")
      (node (ref "U4") (pin "1") (pinfunction "NC_1_1") (pintype "bidirectional"))
    )
    (net (code "100") (name "unconnected-(U4-NC_2-Pad2)") (class "Default")
      (node (ref "U4") (pin "2") (pinfunction "NC_2_2") (pintype "bidirectional"))
    )
    (net (code "101") (name "unconnected-(U4-NC_3-Pad3)") (class "Default")
      (node (ref "U4") (pin "3") (pinfunction "NC_3_3") (pintype "bidirectional"))
    )
    (net (code "102") (name "unconnected-(U4-NC_4-Pad7)") (class "Default")
      (node (ref "U4") (pin "7") (pinfunction "NC_4_7") (pintype "bidirectional"))
    )
    (net (code "103") (name "unconnected-(U8-NC-Pad4)") (class "Default")
      (node (ref "U8") (pin "4") (pinfunction "NC_4") (pintype "no_connect"))
    )
    (net (code "104") (name "unconnected-(U9-EN-Pad4)") (class "Default")
      (node (ref "U9") (pin "4") (pinfunction "EN_4") (pintype "input"))
    )
    (net (code "105") (name "unconnected-(U17-AUX_CL-Pad7)") (class "Default")
      (node (ref "U17") (pin "7") (pinfunction "AUX_CL_7") (pintype "bidirectional"))
    )
    (net (code "106") (name "unconnected-(U17-AUX_DA-Pad6)") (class "Default")
      (node (ref "U17") (pin "6") (pinfunction "AUX_DA_6") (pintype "bidirectional"))
    )
    (net (code "107") (name "unconnected-(U17-EP-Pad25)") (class "Default")
      (node (ref "U17") (pin "25") (pinfunction "EP_25") (pintype "bidirectional"))
    )
    (net (code "108") (name "unconnected-(U17-NC_1-Pad2)") (class "Default")
      (node (ref "U17") (pin "2") (pinfunction "NC_1_2") (pintype "bidirectional"))
    )
    (net (code "109") (name "unconnected-(U17-NC_2-Pad3)") (class "Default")
      (node (ref "U17") (pin "3") (pinfunction "NC_2_3") (pintype "bidirectional"))
    )
    (net (code "110") (name "unconnected-(U17-NC_3-Pad4)") (class "Default")
      (node (ref "U17") (pin "4") (pinfunction "NC_3_4") (pintype "bidirectional"))
    )
    (net (code "111") (name "unconnected-(U17-NC_4-Pad5)") (class "Default")
      (node (ref "U17") (pin "5") (pinfunction "NC_4_5") (pintype "bidirectional"))
    )
    (net (code "112") (name "unconnected-(U17-NC_5-Pad14)") (class "Default")
      (node (ref "U17") (pin "14") (pinfunction "NC_5_14") (pintype "bidirectional"))
    )
    (net (code "113") (name "unconnected-(U17-NC_6-Pad15)") (class "Default")
      (node (ref "U17") (pin "15") (pinfunction "NC_6_15") (pintype "bidirectional"))
    )
    (net (code "114") (name "unconnected-(U17-NC_7-Pad16)") (class "Default")
      (node (ref "U17") (pin "16") (pinfunction "NC_7_16") (pintype "bidirectional"))
    )
    (net (code "115") (name "unconnected-(U17-NC_8-Pad17)") (class "Default")
      (node (ref "U17") (pin "17") (pinfunction "NC_8_17") (pintype "bidirectional"))
    )
    (net (code "116") (name "unconnected-(U17-RESV_1-Pad19)") (class "Default")
      (node (ref "U17") (pin "19") (pinfunction "RESV_1_19") (pintype "bidirectional"))
    )
    (net (code "117") (name "unconnected-(U17-RESV_2-Pad21)") (class "Default")
      (node (ref "U17") (pin "21") (pinfunction "RESV_2_21") (pintype "bidirectional"))
    )
    (net (code "118") (name "unconnected-(U17-RESV_3-Pad22)") (class "Default")
      (node (ref "U17") (pin "22") (pinfunction "RESV_3_22") (pintype "bidirectional"))
    )
    (net (code "119") (name "unconnected-(U18-EN-Pad4)") (class "Default")
      (node (ref "U18") (pin "4") (pinfunction "EN_4") (pintype "input"))
    )
  )
)
